# 12V10A_supply.net
KiCad netlist of a schematic drawn in EAGLE
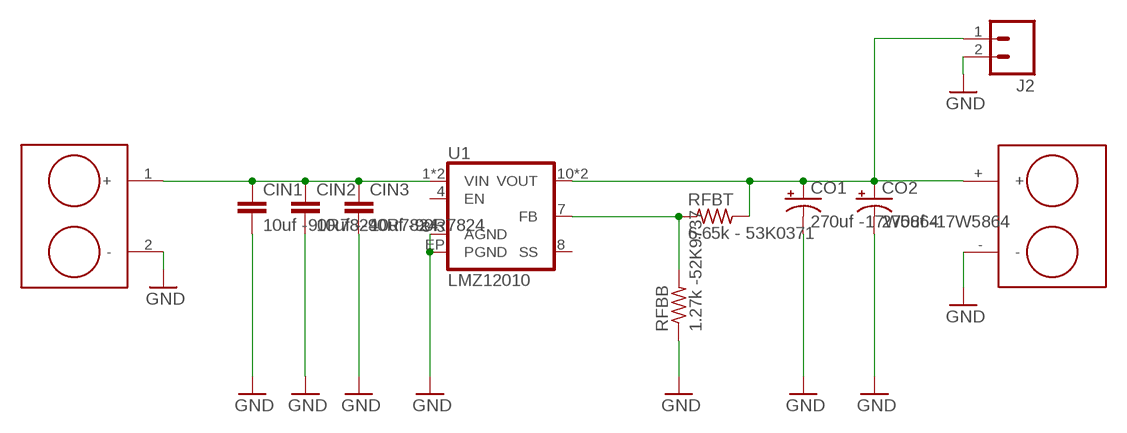
[diagram p0: schematic, sheet 1]

(export (version "E")
  (design (tool "Eeschema 10.0.6"))
  (components
    (comp (ref "CIN1")
      (value "10uf -90R7824")
      (footprint "eagle-import:C1210")
      (libsource (lib "eagle-import") (part "C-EUC1210"))
    )
    (comp (ref "CIN2")
      (value "10uf --90R7824")
      (footprint "eagle-import:C1210")
      (libsource (lib "eagle-import") (part "C-EUC1210"))
    )
    (comp (ref "CIN3")
      (value "10uf -90R7824")
      (footprint "eagle-import:C1210")
      (libsource (lib "eagle-import") (part "C-EUC1210"))
    )
    (comp (ref "CO1")
      (value "270uf -17W5864")
      (footprint "eagle-import:JC0CAP")
      (libsource (lib "eagle-import") (part "NPCAP-PXA-CAP"))
    )
    (comp (ref "CO2")
      (value "270uf -17W5864")
      (footprint "eagle-import:JC0CAP")
      (libsource (lib "eagle-import") (part "NPCAP-PXA-CAP"))
    )
    (comp (ref "J1")
      (value "5569-02A2MS-225")
      (footprint "eagle-import:0050362375")
      (libsource (lib "eagle-import") (part "5569-02A2MS-225"))
    )
    (comp (ref "J2")
      (value "M02PTH")
      (footprint "eagle-import:1X02")
      (libsource (lib "eagle-import") (part "M02PTH"))
    )
    (comp (ref "J3")
      (value "MC24356")
      (footprint "eagle-import:2PINTERMINAL")
      (libsource (lib "eagle-import") (part "MC24356"))
    )
    (comp (ref "RFBB")
      (value "1.27k -52K9737")
      (footprint "eagle-import:M0805")
      (libsource (lib "eagle-import") (part "R-US_M0805"))
    )
    (comp (ref "RFBT")
      (value "6.65k - 53K0371")
      (footprint "eagle-import:M0805")
      (libsource (lib "eagle-import") (part "R-US_M0805"))
    )
    (comp (ref "U1")
      (value "LMZ12010")
      (footprint "eagle-import:TO-PMOD-11")
      (libsource (lib "eagle-import") (part "LMZ12010"))
    )
  )
  (nets
    (net (code "1") (name "GND") (class "Default")
      (node (ref "CIN1") (pin "2") (pinfunction "2_2") (pintype "passive"))
      (node (ref "CIN2") (pin "2") (pinfunction "2_2") (pintype "passive"))
      (node (ref "CIN3") (pin "2") (pinfunction "2_2") (pintype "passive"))
      (node (ref "CO1") (pin "-") (pinfunction "-_-") (pintype "passive"))
      (node (ref "CO2") (pin "-") (pinfunction "-_-") (pintype "passive"))
      (node (ref "J1") (pin "2") (pinfunction "-_2") (pintype "bidirectional"))
      (node (ref "J2") (pin "2") (pinfunction "2_2") (pintype "passive"))
      (node (ref "J3") (pin "-") (pinfunction "-_-") (pintype "bidirectional"))
      (node (ref "RFBB") (pin "1") (pinfunction "1_1") (pintype "passive"))
      (node (ref "U1") (pin "3") (pinfunction "AGND_3") (pintype "bidirectional"))
      (node (ref "U1") (pin "5") (pinfunction "AGND_5") (pintype "bidirectional"))
      (node (ref "U1") (pin "6") (pinfunction "AGND_6") (pintype "bidirectional"))
      (node (ref "U1") (pin "EP") (pinfunction "PGND_EP") (pintype "bidirectional"))
    )
    (net (code "2") (name "Net-(CO1-Pad+)") (class "Default")
      (node (ref "CO1") (pin "+") (pinfunction "+_+") (pintype "passive"))
      (node (ref "CO2") (pin "+") (pinfunction "+_+") (pintype "passive"))
      (node (ref "J2") (pin "1") (pinfunction "1_1") (pintype "passive"))
      (node (ref "J3") (pin "+") (pinfunction "+_+") (pintype "bidirectional"))
      (node (ref "RFBT") (pin "2") (pinfunction "2_2") (pintype "passive"))
      (node (ref "U1") (pin "10") (pinfunction "VOUT_10") (pintype "bidirectional"))
      (node (ref "U1") (pin "11") (pinfunction "VOUT_11") (pintype "bidirectional"))
    )
    (net (code "3") (name "Net-(J1-+)") (class "Default")
      (node (ref "CIN1") (pin "1") (pinfunction "1_1") (pintype "passive"))
      (node (ref "CIN2") (pin "1") (pinfunction "1_1") (pintype "passive"))
      (node (ref "CIN3") (pin "1") (pinfunction "1_1") (pintype "passive"))
      (node (ref "J1") (pin "1") (pinfunction "+_1") (pintype "bidirectional"))
      (node (ref "U1") (pin "1") (pinfunction "VIN_1") (pintype "bidirectional"))
      (node (ref "U1") (pin "2") (pinfunction "VIN_2") (pintype "bidirectional"))
    )
    (net (code "4") (name "Net-(U1-FB)") (class "Default")
      (node (ref "RFBB") (pin "2") (pinfunction "2_2") (pintype "passive"))
      (node (ref "RFBT") (pin "1") (pinfunction "1_1") (pintype "passive"))
      (node (ref "U1") (pin "7") (pinfunction "FB_7") (pintype "bidirectional"))
    )
    (net (code "5") (name "unconnected-(U1-EN-Pad4)") (class "Default")
      (node (ref "U1") (pin "4") (pinfunction "EN_4") (pintype "bidirectional"))
    )
    (net (code "6") (name "unconnected-(U1-SS-Pad8)") (class "Default")
      (node (ref "U1") (pin "8") (pinfunction "SS_8") (pintype "bidirectional"))
    )
  )
)
